# Connectors.net
KiCad netlist of a schematic drawn in Altium Designer
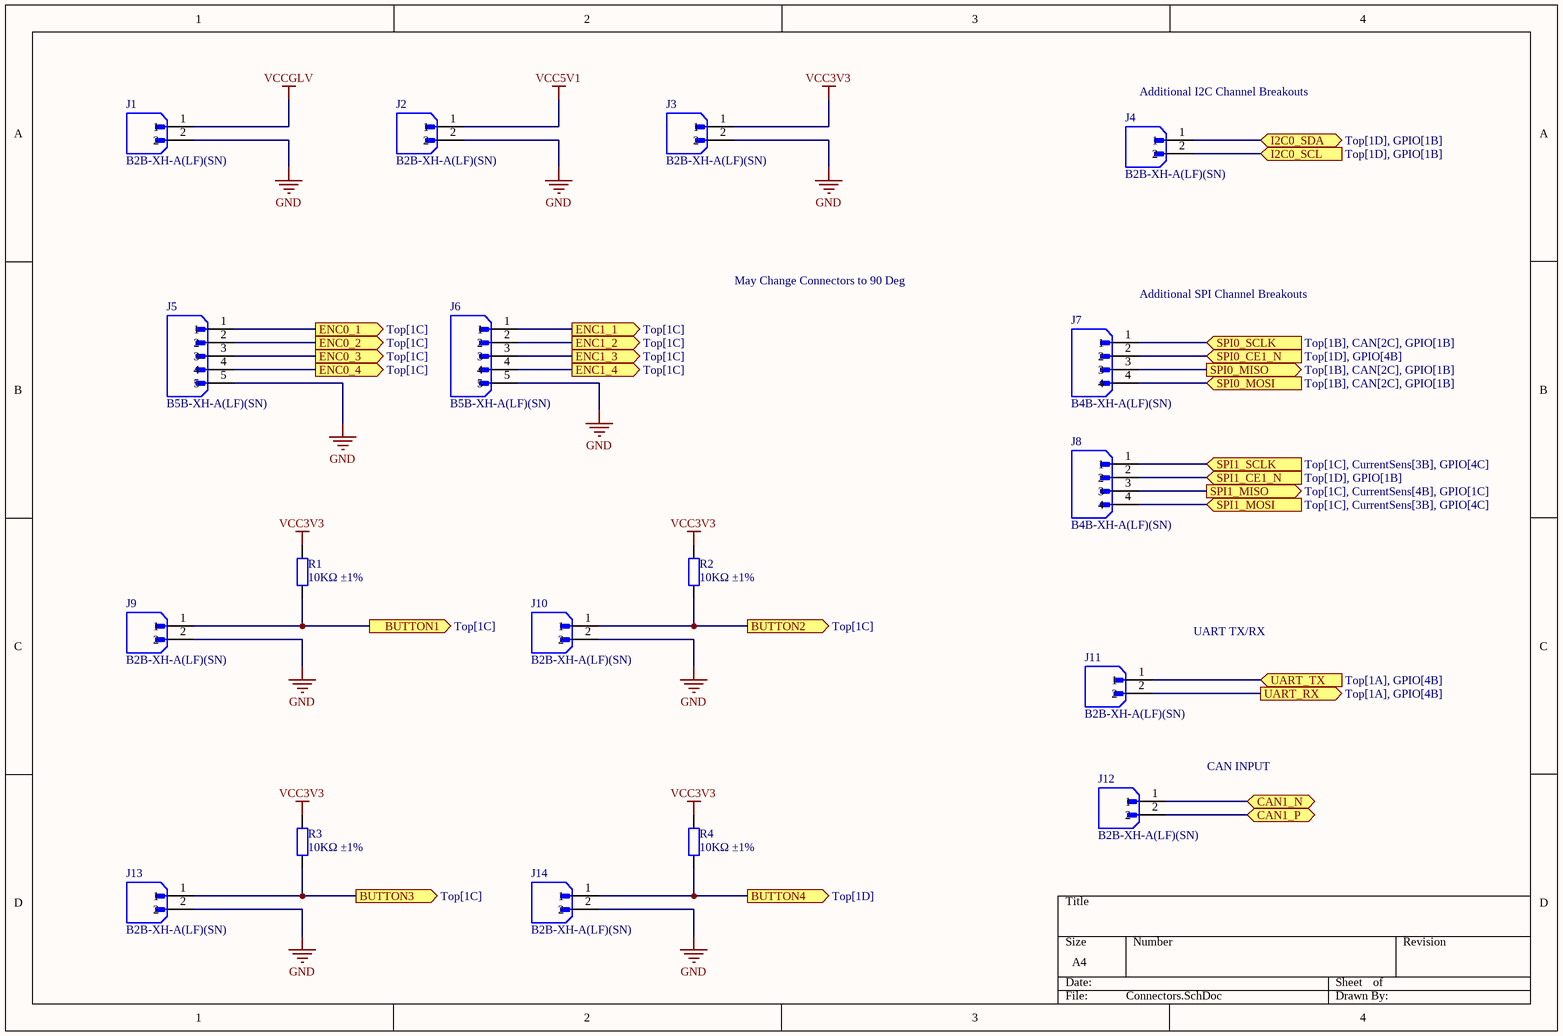
[diagram p0: Connectors.SchDoc]

(export (version "E")
  (design (tool "Eeschema 10.0.6"))
  (components
    (comp (ref "J1")
      (value "B2B-XH-A(LF)(SN)")
      (footprint "JST_B2B-XH-A(LF)(SN)")
      (description "Connector Header Through Hole 2 position 0.098 (2.50mm)")
      (fields (field (name "MF") "JST Sales"))
      (libsource (lib "B2B-XH-A_LF__SN_") (part "B2B-XH-A(LF)(SN)"))
    )
    (comp (ref "J2")
      (value "B2B-XH-A(LF)(SN)")
      (footprint "JST_B2B-XH-A(LF)(SN)")
      (description "Connector Header Through Hole 2 position 0.098 (2.50mm)")
      (fields (field (name "MF") "JST Sales"))
      (libsource (lib "B2B-XH-A_LF__SN_") (part "B2B-XH-A(LF)(SN)"))
    )
    (comp (ref "J3")
      (value "B2B-XH-A(LF)(SN)")
      (footprint "JST_B2B-XH-A(LF)(SN)")
      (description "Connector Header Through Hole 2 position 0.098 (2.50mm)")
      (fields (field (name "MF") "JST Sales"))
      (libsource (lib "B2B-XH-A_LF__SN_") (part "B2B-XH-A(LF)(SN)"))
    )
    (comp (ref "J4")
      (value "B2B-XH-A(LF)(SN)")
      (footprint "JST_B2B-XH-A(LF)(SN)")
      (description "Connector Header Through Hole 2 position 0.098 (2.50mm)")
      (fields (field (name "MF") "JST Sales"))
      (libsource (lib "B2B-XH-A_LF__SN_") (part "B2B-XH-A(LF)(SN)"))
    )
    (comp (ref "J5")
      (value "B5B-XH-A(LF)(SN)")
      (footprint "JST_B5B-XH-A(LF)(SN)")
      (description "Connector Header Through Hole 5 position 0.098 (2.50mm)")
      (fields (field (name "MF") "JST Sales America Inc."))
      (libsource (lib "B5B-XH-A_LF__SN_") (part "B5B-XH-A(LF)(SN)"))
    )
    (comp (ref "J6")
      (value "B5B-XH-A(LF)(SN)")
      (footprint "JST_B5B-XH-A(LF)(SN)")
      (description "Connector Header Through Hole 5 position 0.098 (2.50mm)")
      (fields (field (name "MF") "JST Sales America Inc."))
      (libsource (lib "B5B-XH-A_LF__SN_") (part "B5B-XH-A(LF)(SN)"))
    )
    (comp (ref "J7")
      (value "B4B-XH-A(LF)(SN)")
      (footprint "JST_B4B-XH-A(LF)(SN)")
      (description "Connector Header Through Hole 4 position 0.098 (2.50mm)")
      (fields (field (name "MF") "JST Sales"))
      (libsource (lib "B4B-XH-A_LF__SN_") (part "B4B-XH-A(LF)(SN)"))
    )
    (comp (ref "J8")
      (value "B4B-XH-A(LF)(SN)")
      (footprint "JST_B4B-XH-A(LF)(SN)")
      (description "Connector Header Through Hole 4 position 0.098 (2.50mm)")
      (fields (field (name "MF") "JST Sales"))
      (libsource (lib "B4B-XH-A_LF__SN_") (part "B4B-XH-A(LF)(SN)"))
    )
    (comp (ref "J9")
      (value "B2B-XH-A(LF)(SN)")
      (footprint "JST_B2B-XH-A(LF)(SN)")
      (description "Connector Header Through Hole 2 position 0.098 (2.50mm)")
      (fields (field (name "MF") "JST Sales"))
      (libsource (lib "B2B-XH-A_LF__SN_") (part "B2B-XH-A(LF)(SN)"))
    )
    (comp (ref "J10")
      (value "B2B-XH-A(LF)(SN)")
      (footprint "JST_B2B-XH-A(LF)(SN)")
      (description "Connector Header Through Hole 2 position 0.098 (2.50mm)")
      (fields (field (name "MF") "JST Sales"))
      (libsource (lib "B2B-XH-A_LF__SN_") (part "B2B-XH-A(LF)(SN)"))
    )
    (comp (ref "J11")
      (value "B2B-XH-A(LF)(SN)")
      (footprint "JST_B2B-XH-A(LF)(SN)")
      (description "Connector Header Through Hole 2 position 0.098 (2.50mm)")
      (fields (field (name "MF") "JST Sales"))
      (libsource (lib "B2B-XH-A_LF__SN_") (part "B2B-XH-A(LF)(SN)"))
    )
    (comp (ref "J12")
      (value "B2B-XH-A(LF)(SN)")
      (footprint "JST_B2B-XH-A(LF)(SN)")
      (description "Connector Header Through Hole 2 position 0.098 (2.50mm)")
      (fields (field (name "MF") "JST Sales"))
      (libsource (lib "B2B-XH-A_LF__SN_") (part "B2B-XH-A(LF)(SN)"))
    )
    (comp (ref "J13")
      (value "B2B-XH-A(LF)(SN)")
      (footprint "JST_B2B-XH-A(LF)(SN)")
      (description "Connector Header Through Hole 2 position 0.098 (2.50mm)")
      (fields (field (name "MF") "JST Sales"))
      (libsource (lib "B2B-XH-A_LF__SN_") (part "B2B-XH-A(LF)(SN)"))
    )
    (comp (ref "J14")
      (value "B2B-XH-A(LF)(SN)")
      (footprint "JST_B2B-XH-A(LF)(SN)")
      (description "Connector Header Through Hole 2 position 0.098 (2.50mm)")
      (fields (field (name "MF") "JST Sales"))
      (libsource (lib "B2B-XH-A_LF__SN_") (part "B2B-XH-A(LF)(SN)"))
    )
    (comp (ref "R1")
      (value "10KΩ ±1%")
      (footprint "0402_R")
      (description "Chip resistor")
      (fields (field (name "MANUFACTURER") "Uniroyal Elec") (field (name "PARTNUMBER") "0402WGF1002TCE"))
      (libsource (lib "RES") (part "0402 10K (1002) 1%"))
    )
    (comp (ref "R2")
      (value "10KΩ ±1%")
      (footprint "0402_R")
      (description "Chip resistor")
      (fields (field (name "MANUFACTURER") "Uniroyal Elec") (field (name "PARTNUMBER") "0402WGF1002TCE"))
      (libsource (lib "RES") (part "0402 10K (1002) 1%"))
    )
    (comp (ref "R3")
      (value "10KΩ ±1%")
      (footprint "0402_R")
      (description "Chip resistor")
      (fields (field (name "MANUFACTURER") "Uniroyal Elec") (field (name "PARTNUMBER") "0402WGF1002TCE"))
      (libsource (lib "RES") (part "0402 10K (1002) 1%"))
    )
    (comp (ref "R4")
      (value "10KΩ ±1%")
      (footprint "0402_R")
      (description "Chip resistor")
      (fields (field (name "MANUFACTURER") "Uniroyal Elec") (field (name "PARTNUMBER") "0402WGF1002TCE"))
      (libsource (lib "RES") (part "0402 10K (1002) 1%"))
    )
  )
  (nets
    (net (code "1") (name "/BUTTON1") (class "Default")
      (node (ref "J9") (pin "1") (pinfunction "1_1") (pintype "passive"))
      (node (ref "R1") (pin "1") (pinfunction "1_1") (pintype "passive"))
    )
    (net (code "2") (name "/BUTTON2") (class "Default")
      (node (ref "J10") (pin "1") (pinfunction "1_1") (pintype "passive"))
      (node (ref "R2") (pin "1") (pinfunction "1_1") (pintype "passive"))
    )
    (net (code "3") (name "/BUTTON3") (class "Default")
      (node (ref "J13") (pin "1") (pinfunction "1_1") (pintype "passive"))
      (node (ref "R3") (pin "1") (pinfunction "1_1") (pintype "passive"))
    )
    (net (code "4") (name "/BUTTON4") (class "Default")
      (node (ref "J14") (pin "1") (pinfunction "1_1") (pintype "passive"))
      (node (ref "R4") (pin "1") (pinfunction "1_1") (pintype "passive"))
    )
    (net (code "5") (name "/CAN1_N") (class "Default")
      (node (ref "J12") (pin "1") (pinfunction "1_1") (pintype "passive"))
    )
    (net (code "6") (name "/CAN1_P") (class "Default")
      (node (ref "J12") (pin "2") (pinfunction "2_2") (pintype "passive"))
    )
    (net (code "7") (name "/ENC0_1") (class "Default")
      (node (ref "J5") (pin "1") (pinfunction "1_1") (pintype "passive"))
    )
    (net (code "8") (name "/ENC0_2") (class "Default")
      (node (ref "J5") (pin "2") (pinfunction "2_2") (pintype "passive"))
    )
    (net (code "9") (name "/ENC0_3") (class "Default")
      (node (ref "J5") (pin "3") (pinfunction "3_3") (pintype "passive"))
    )
    (net (code "10") (name "/ENC0_4") (class "Default")
      (node (ref "J5") (pin "4") (pinfunction "4_4") (pintype "passive"))
    )
    (net (code "11") (name "/ENC1_1") (class "Default")
      (node (ref "J6") (pin "1") (pinfunction "1_1") (pintype "passive"))
    )
    (net (code "12") (name "/ENC1_2") (class "Default")
      (node (ref "J6") (pin "2") (pinfunction "2_2") (pintype "passive"))
    )
    (net (code "13") (name "/ENC1_3") (class "Default")
      (node (ref "J6") (pin "3") (pinfunction "3_3") (pintype "passive"))
    )
    (net (code "14") (name "/ENC1_4") (class "Default")
      (node (ref "J6") (pin "4") (pinfunction "4_4") (pintype "passive"))
    )
    (net (code "15") (name "/I2C0_SCL") (class "Default")
      (node (ref "J4") (pin "2") (pinfunction "2_2") (pintype "passive"))
    )
    (net (code "16") (name "/I2C0_SDA") (class "Default")
      (node (ref "J4") (pin "1") (pinfunction "1_1") (pintype "passive"))
    )
    (net (code "17") (name "/SPI0_CE1_N") (class "Default")
      (node (ref "J7") (pin "2") (pinfunction "2_2") (pintype "passive"))
    )
    (net (code "18") (name "/SPI0_MISO") (class "Default")
      (node (ref "J7") (pin "3") (pinfunction "3_3") (pintype "passive"))
    )
    (net (code "19") (name "/SPI0_MOSI") (class "Default")
      (node (ref "J7") (pin "4") (pinfunction "4_4") (pintype "passive"))
    )
    (net (code "20") (name "/SPI0_SCLK") (class "Default")
      (node (ref "J7") (pin "1") (pinfunction "1_1") (pintype "passive"))
    )
    (net (code "21") (name "/SPI1_CE1_N") (class "Default")
      (node (ref "J8") (pin "2") (pinfunction "2_2") (pintype "passive"))
    )
    (net (code "22") (name "/SPI1_MISO") (class "Default")
      (node (ref "J8") (pin "3") (pinfunction "3_3") (pintype "passive"))
    )
    (net (code "23") (name "/SPI1_MOSI") (class "Default")
      (node (ref "J8") (pin "4") (pinfunction "4_4") (pintype "passive"))
    )
    (net (code "24") (name "/SPI1_SCLK") (class "Default")
      (node (ref "J8") (pin "1") (pinfunction "1_1") (pintype "passive"))
    )
    (net (code "25") (name "/UART_RX") (class "Default")
      (node (ref "J11") (pin "2") (pinfunction "2_2") (pintype "passive"))
    )
    (net (code "26") (name "/UART_TX") (class "Default")
      (node (ref "J11") (pin "1") (pinfunction "1_1") (pintype "passive"))
    )
    (net (code "27") (name "GND") (class "Default")
      (node (ref "J1") (pin "2") (pinfunction "2_2") (pintype "passive"))
      (node (ref "J10") (pin "2") (pinfunction "2_2") (pintype "passive"))
      (node (ref "J13") (pin "2") (pinfunction "2_2") (pintype "passive"))
      (node (ref "J14") (pin "2") (pinfunction "2_2") (pintype "passive"))
      (node (ref "J2") (pin "2") (pinfunction "2_2") (pintype "passive"))
      (node (ref "J3") (pin "2") (pinfunction "2_2") (pintype "passive"))
      (node (ref "J5") (pin "5") (pinfunction "5_5") (pintype "passive"))
      (node (ref "J6") (pin "5") (pinfunction "5_5") (pintype "passive"))
      (node (ref "J9") (pin "2") (pinfunction "2_2") (pintype "passive"))
    )
    (net (code "28") (name "VCC3V3") (class "Default")
      (node (ref "J3") (pin "1") (pinfunction "1_1") (pintype "passive"))
      (node (ref "R1") (pin "2") (pinfunction "2_2") (pintype "passive"))
      (node (ref "R2") (pin "2") (pinfunction "2_2") (pintype "passive"))
      (node (ref "R3") (pin "2") (pinfunction "2_2") (pintype "passive"))
      (node (ref "R4") (pin "2") (pinfunction "2_2") (pintype "passive"))
    )
    (net (code "29") (name "VCC5V1") (class "Default")
      (node (ref "J2") (pin "1") (pinfunction "1_1") (pintype "passive"))
    )
    (net (code "30") (name "VCCGLV") (class "Default")
      (node (ref "J1") (pin "1") (pinfunction "1_1") (pintype "passive"))
    )
  )
)
